# Full_Pow_Schematic1_sch.net
KiCad netlist of a schematic drawn in EAGLE
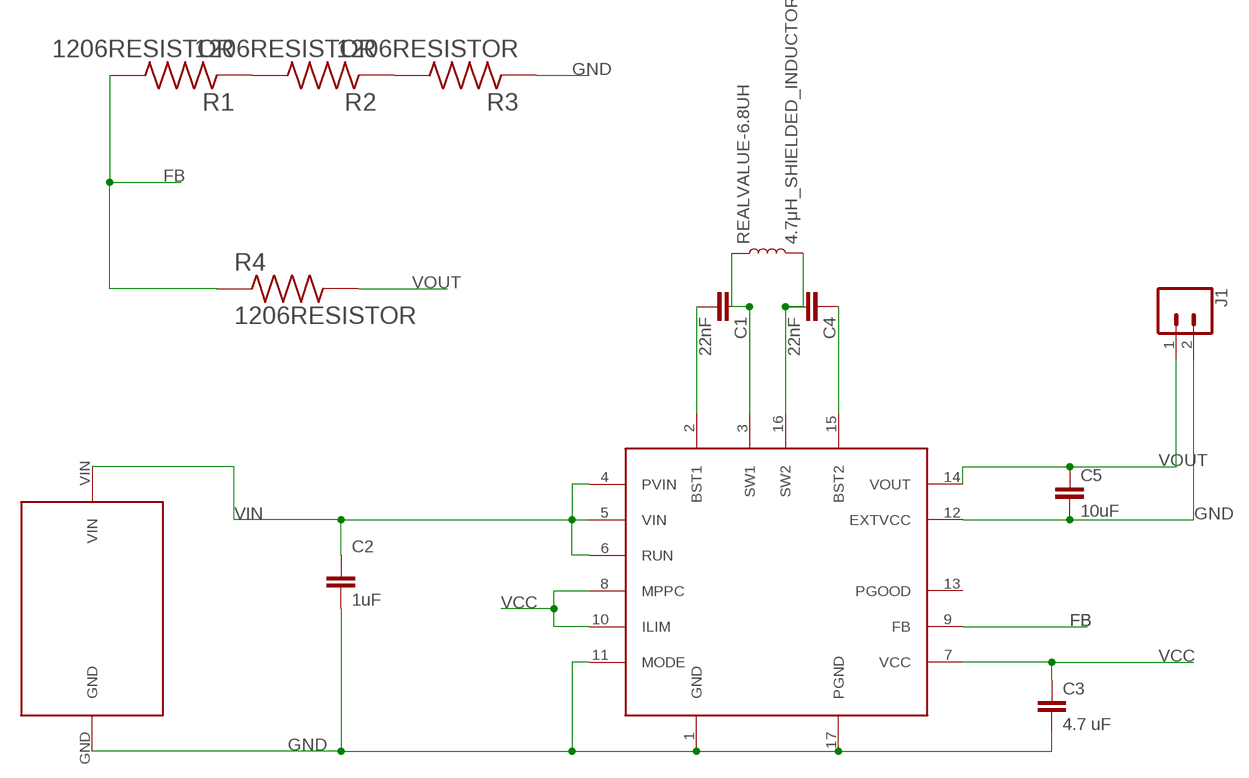
[diagram p0: schematic, sheet 1]

(export (version "E")
  (design (tool "Eeschema 10.0.6"))
  (components
    (comp (ref "C1")
      (value "22nF")
      (footprint "eagle-import:0402")
      (libsource (lib "eagle-import") (part "22NF/22,000PF-0603-25V-10%-X7R"))
    )
    (comp (ref "C2")
      (value "1uF")
      (footprint "eagle-import:0402")
      (libsource (lib "eagle-import") (part "22NF/22,000PF-0603-25V-10%-X7R"))
    )
    (comp (ref "C3")
      (value "4.7 uF")
      (footprint "eagle-import:0402")
      (libsource (lib "eagle-import") (part "22NF/22,000PF-0603-25V-10%-X7R"))
    )
    (comp (ref "C4")
      (value "22nF")
      (footprint "eagle-import:0402")
      (libsource (lib "eagle-import") (part "22NF/22,000PF-0603-25V-10%-X7R"))
    )
    (comp (ref "C5")
      (value "10uF")
      (footprint "eagle-import:0402")
      (libsource (lib "eagle-import") (part "22NF/22,000PF-0603-25V-10%-X7R"))
    )
    (comp (ref "J1")
      (value "CONN_02")
      (footprint "eagle-import:1X02")
      (libsource (lib "eagle-import") (part "CONN_02"))
    )
    (comp (ref "R1")
      (value "1206RESISTOR")
      (footprint "eagle-import:RESC3116X65N")
      (fields (field (name "MF") "Yageo") (field (name "MP") "RC1206JR-0713RL"))
      (libsource (lib "eagle-import") (part "1206RESISTOR"))
    )
    (comp (ref "R2")
      (value "1206RESISTOR")
      (footprint "eagle-import:RESC3116X65N")
      (fields (field (name "MF") "Yageo") (field (name "MP") "RC1206JR-0713RL"))
      (libsource (lib "eagle-import") (part "1206RESISTOR"))
    )
    (comp (ref "R3")
      (value "1206RESISTOR")
      (footprint "eagle-import:RESC3116X65N")
      (fields (field (name "MF") "Yageo") (field (name "MP") "RC1206JR-0713RL"))
      (libsource (lib "eagle-import") (part "1206RESISTOR"))
    )
    (comp (ref "R4")
      (value "1206RESISTOR")
      (footprint "eagle-import:RESC3116X65N")
      (fields (field (name "MF") "Yageo") (field (name "MP") "RC1206JR-0713RL"))
      (libsource (lib "eagle-import") (part "1206RESISTOR"))
    )
    (comp (ref "REALVALUE-6.8UH")
      (value "4.7μH_SHIELDED_INDUCTOR")
      (footprint "eagle-import:1008(2520)")
      (libsource (lib "eagle-import") (part "4.7μH_SHIELDED_INDUCTOR"))
    )
    (comp (ref "U$1")
      (value "LTC3130")
      (footprint "eagle-import:SOP50P490X110-17N")
      (libsource (lib "eagle-import") (part "LTC3130"))
    )
    (comp (ref "U$2")
      (value "SM101K12L")
      (footprint "eagle-import:SM101K12L")
      (libsource (lib "eagle-import") (part "SM101K12L"))
    )
  )
  (nets
    (net (code "1") (name "/FB") (class "Default")
      (node (ref "R1") (pin "2") (pinfunction "2_2") (pintype "passive"))
      (node (ref "R4") (pin "1") (pinfunction "1_1") (pintype "passive"))
      (node (ref "U$1") (pin "9") (pinfunction "FB_9") (pintype "bidirectional"))
    )
    (net (code "2") (name "/GND") (class "Default")
      (node (ref "C2") (pin "2") (pinfunction "2_2") (pintype "passive"))
      (node (ref "C3") (pin "2") (pinfunction "2_2") (pintype "passive"))
      (node (ref "C5") (pin "2") (pinfunction "2_2") (pintype "passive"))
      (node (ref "J1") (pin "2") (pinfunction "2_2") (pintype "passive"))
      (node (ref "R3") (pin "1") (pinfunction "1_1") (pintype "passive"))
      (node (ref "U$1") (pin "1") (pinfunction "GND_1") (pintype "bidirectional"))
      (node (ref "U$1") (pin "11") (pinfunction "MODE_11") (pintype "bidirectional"))
      (node (ref "U$1") (pin "12") (pinfunction "EXTVCC_12") (pintype "bidirectional"))
      (node (ref "U$1") (pin "17") (pinfunction "PGND_17") (pintype "bidirectional"))
      (node (ref "U$2") (pin "GND") (pinfunction "GND_GND") (pintype "bidirectional"))
    )
    (net (code "3") (name "/VCC") (class "Default")
      (node (ref "C3") (pin "1") (pinfunction "1_1") (pintype "passive"))
      (node (ref "U$1") (pin "10") (pinfunction "ILIM_10") (pintype "bidirectional"))
      (node (ref "U$1") (pin "7") (pinfunction "VCC_7") (pintype "bidirectional"))
      (node (ref "U$1") (pin "8") (pinfunction "MPPC_8") (pintype "bidirectional"))
    )
    (net (code "4") (name "/VIN") (class "Default")
      (node (ref "C2") (pin "1") (pinfunction "1_1") (pintype "passive"))
      (node (ref "U$1") (pin "4") (pinfunction "PVIN_4") (pintype "bidirectional"))
      (node (ref "U$1") (pin "5") (pinfunction "VIN_5") (pintype "bidirectional"))
      (node (ref "U$1") (pin "6") (pinfunction "RUN_6") (pintype "bidirectional"))
      (node (ref "U$2") (pin "VIN") (pinfunction "VIN_VIN") (pintype "bidirectional"))
    )
    (net (code "5") (name "/VOUT") (class "Default")
      (node (ref "C5") (pin "1") (pinfunction "1_1") (pintype "passive"))
      (node (ref "J1") (pin "1") (pinfunction "1_1") (pintype "passive"))
      (node (ref "R4") (pin "2") (pinfunction "2_2") (pintype "passive"))
      (node (ref "U$1") (pin "14") (pinfunction "VOUT_14") (pintype "bidirectional"))
    )
    (net (code "6") (name "Net-(R1-Pad1)") (class "Default")
      (node (ref "R1") (pin "1") (pinfunction "1_1") (pintype "passive"))
      (node (ref "R2") (pin "2") (pinfunction "2_2") (pintype "passive"))
    )
    (net (code "7") (name "Net-(R2-Pad1)") (class "Default")
      (node (ref "R2") (pin "1") (pinfunction "1_1") (pintype "passive"))
      (node (ref "R3") (pin "2") (pinfunction "2_2") (pintype "passive"))
    )
    (net (code "8") (name "Net-(U$1-BST1)") (class "Default")
      (node (ref "C1") (pin "2") (pinfunction "2_2") (pintype "passive"))
      (node (ref "U$1") (pin "2") (pinfunction "BST1_2") (pintype "bidirectional"))
    )
    (net (code "9") (name "Net-(U$1-BST2)") (class "Default")
      (node (ref "C4") (pin "1") (pinfunction "1_1") (pintype "passive"))
      (node (ref "U$1") (pin "15") (pinfunction "BST2_15") (pintype "bidirectional"))
    )
    (net (code "10") (name "Net-(U$1-SW1)") (class "Default")
      (node (ref "C1") (pin "1") (pinfunction "1_1") (pintype "passive"))
      (node (ref "REALVALUE-6.8UH") (pin "1") (pinfunction "1_1") (pintype "passive"))
      (node (ref "U$1") (pin "3") (pinfunction "SW1_3") (pintype "bidirectional"))
    )
    (net (code "11") (name "Net-(U$1-SW2)") (class "Default")
      (node (ref "C4") (pin "2") (pinfunction "2_2") (pintype "passive"))
      (node (ref "REALVALUE-6.8UH") (pin "2") (pinfunction "2_2") (pintype "passive"))
      (node (ref "U$1") (pin "16") (pinfunction "SW2_16") (pintype "bidirectional"))
    )
    (net (code "12") (name "unconnected-(U$1-PGOOD-Pad13)") (class "Default")
      (node (ref "U$1") (pin "13") (pinfunction "PGOOD_13") (pintype "bidirectional"))
    )
  )
)
